# SCH_opticaltoqwiic_2024-08-06.net
KiCad netlist of a schematic drawn in EasyEDA
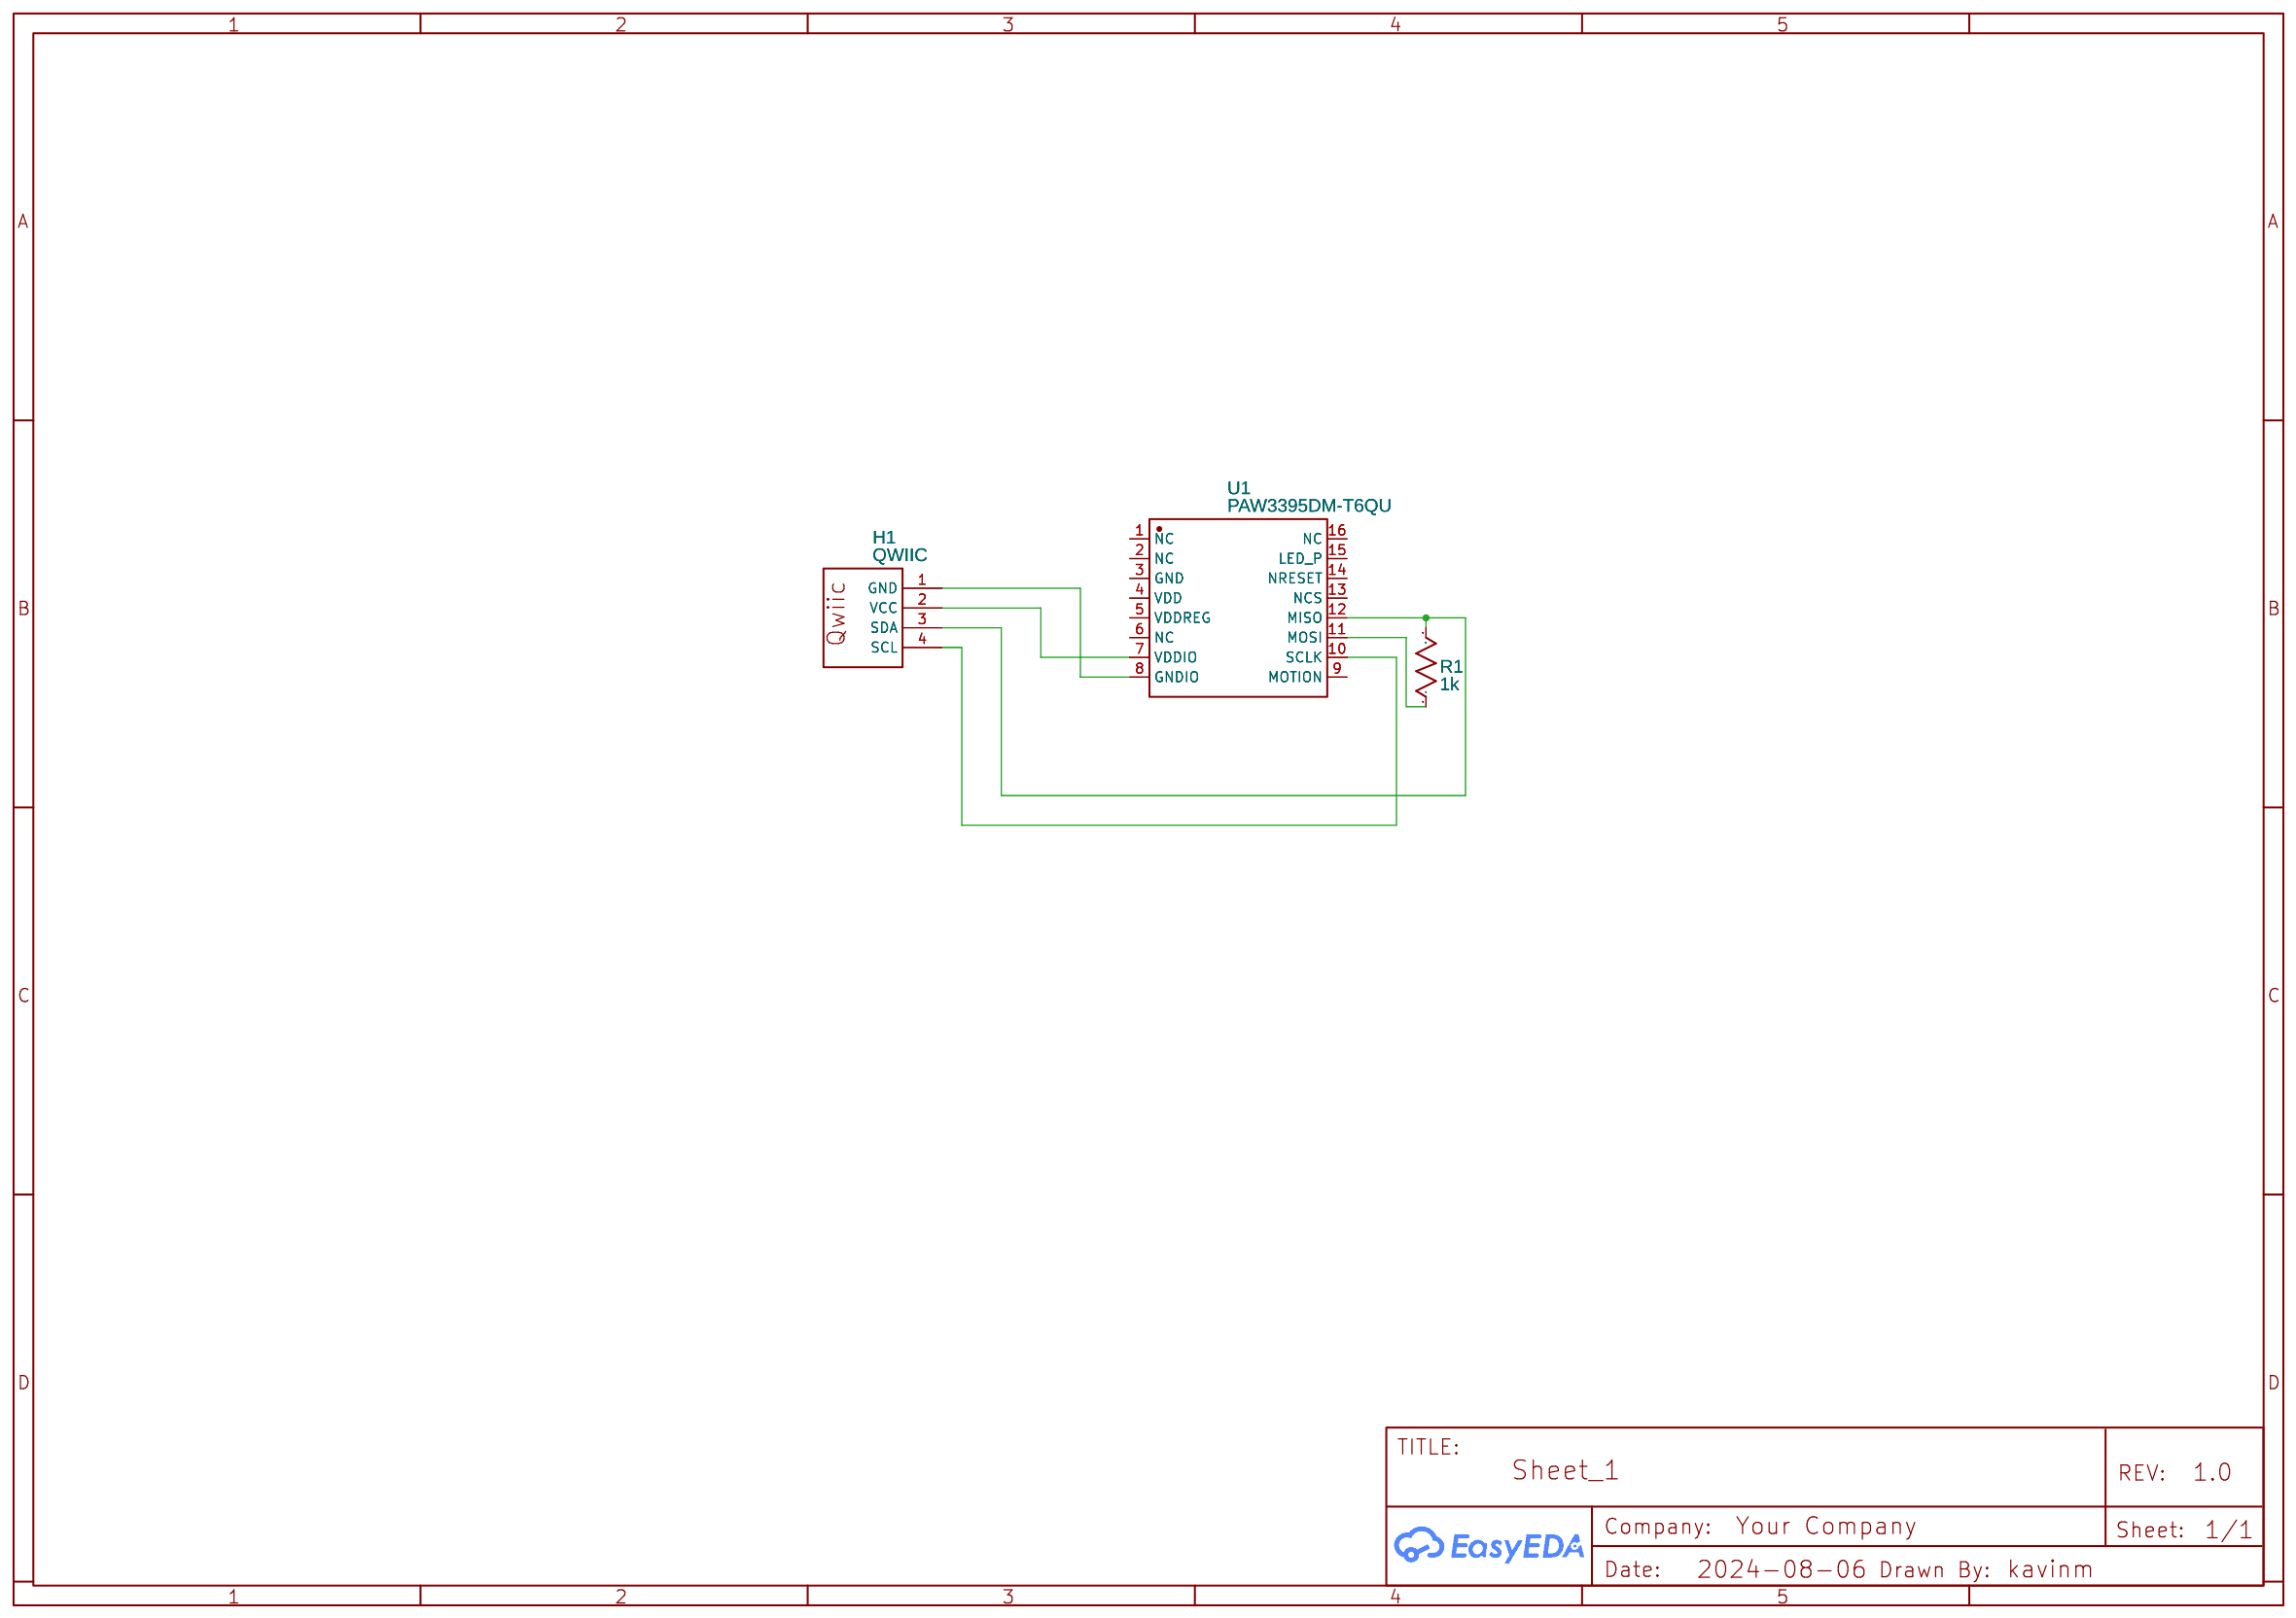
[diagram p0: schematic sheet]

(export (version "E")
  (design (tool "Eeschema 10.0.6"))
  (components
    (comp (ref "H1") (value "QWIIC") (libsource (lib "") (part "QWIIC")))
    (comp (ref "R1") (value "1k") (libsource (lib "") (part "R_0603_US")))
    (comp (ref "U1") (value "PAW3395DM-T6QU") (libsource (lib "") (part "PAW3395DM-T6QU")))
  )
  (nets
    (net (code "1") (name "Net-(H1-GND)") (class "Default")
      (node (ref "H1") (pin "1") (pinfunction "GND_1") (pintype "unspecified"))
      (node (ref "U1") (pin "8") (pinfunction "GNDIO_8") (pintype "unspecified"))
    )
    (net (code "2") (name "Net-(H1-SCL)") (class "Default")
      (node (ref "H1") (pin "4") (pinfunction "SCL_4") (pintype "unspecified"))
      (node (ref "U1") (pin "10") (pinfunction "SCLK_10") (pintype "unspecified"))
    )
    (net (code "3") (name "Net-(H1-SDA)") (class "Default")
      (node (ref "H1") (pin "3") (pinfunction "SDA_3") (pintype "unspecified"))
      (node (ref "R1") (pin "2") (pinfunction "2_2") (pintype "unspecified"))
      (node (ref "U1") (pin "12") (pinfunction "MISO_12") (pintype "unspecified"))
    )
    (net (code "4") (name "Net-(H1-VCC)") (class "Default")
      (node (ref "H1") (pin "2") (pinfunction "VCC_2") (pintype "unspecified"))
      (node (ref "U1") (pin "7") (pinfunction "VDDIO_7") (pintype "unspecified"))
    )
    (net (code "5") (name "Net-(U1-MOSI)") (class "Default")
      (node (ref "R1") (pin "1") (pinfunction "1_1") (pintype "unspecified"))
      (node (ref "U1") (pin "11") (pinfunction "MOSI_11") (pintype "unspecified"))
    )
    (net (code "6") (name "unconnected-(U1-GND-Pad3)") (class "Default")
      (node (ref "U1") (pin "3") (pinfunction "GND_3") (pintype "unspecified"))
    )
    (net (code "7") (name "unconnected-(U1-LED_P-Pad15)") (class "Default")
      (node (ref "U1") (pin "15") (pinfunction "LED_P_15") (pintype "unspecified"))
    )
    (net (code "8") (name "unconnected-(U1-MOTION-Pad9)") (class "Default")
      (node (ref "U1") (pin "9") (pinfunction "MOTION_9") (pintype "unspecified"))
    )
    (net (code "9") (name "unconnected-(U1-NC-Pad1)") (class "Default")
      (node (ref "U1") (pin "1") (pinfunction "NC_1") (pintype "unspecified"))
    )
    (net (code "10") (name "unconnected-(U1-NC-Pad2)") (class "Default")
      (node (ref "U1") (pin "2") (pinfunction "NC_2") (pintype "unspecified"))
    )
    (net (code "11") (name "unconnected-(U1-NC-Pad6)") (class "Default")
      (node (ref "U1") (pin "6") (pinfunction "NC_6") (pintype "unspecified"))
    )
    (net (code "12") (name "unconnected-(U1-NC-Pad16)") (class "Default")
      (node (ref "U1") (pin "16") (pinfunction "NC_16") (pintype "unspecified"))
    )
    (net (code "13") (name "unconnected-(U1-NCS-Pad13)") (class "Default")
      (node (ref "U1") (pin "13") (pinfunction "NCS_13") (pintype "unspecified"))
    )
    (net (code "14") (name "unconnected-(U1-NRESET-Pad14)") (class "Default")
      (node (ref "U1") (pin "14") (pinfunction "NRESET_14") (pintype "unspecified"))
    )
    (net (code "15") (name "unconnected-(U1-VDD-Pad4)") (class "Default")
      (node (ref "U1") (pin "4") (pinfunction "VDD_4") (pintype "unspecified"))
    )
    (net (code "16") (name "unconnected-(U1-VDDREG-Pad5)") (class "Default")
      (node (ref "U1") (pin "5") (pinfunction "VDDREG_5") (pintype "unspecified"))
    )
  )
)
